# CAPT-B1-02_Cap_Touch_Matrix_FeatherWing.net
KiCad netlist of a schematic drawn in EAGLE
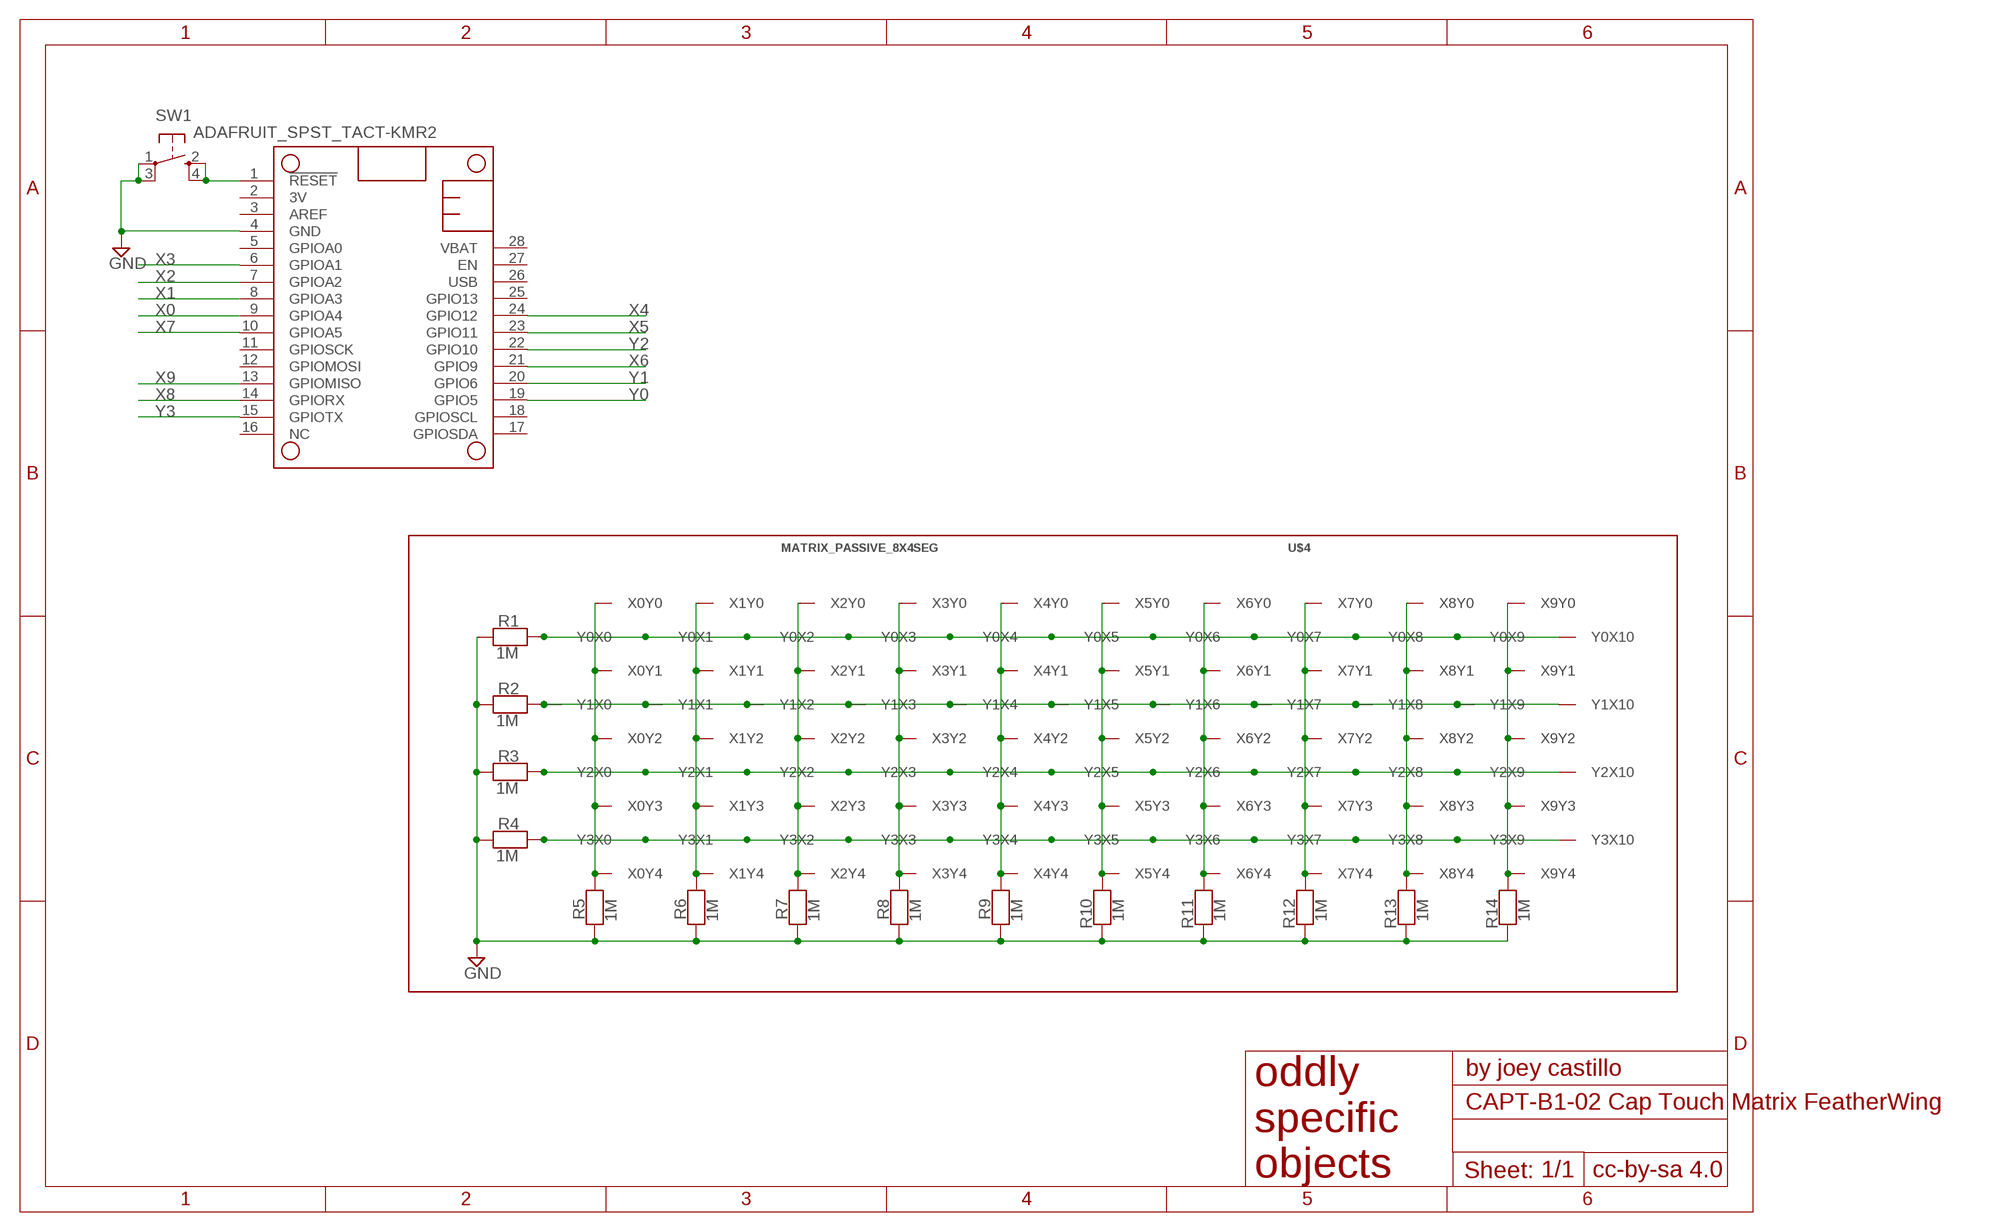
[diagram p0: schematic, sheet 1]

(export (version "E")
  (design (tool "Eeschema 10.0.6"))
  (components
    (comp (ref "MS2")
      (value "MICROBUILDER_FEATHERWING_NOHOLES")
      (footprint "eagle-import:MICROBUILDER_FEATHERWING_NOHOLES")
      (libsource (lib "eagle-import") (part "MICROBUILDER_FEATHERWING_NOHOLES"))
    )
    (comp (ref "R1")
      (value "1M")
      (footprint "eagle-import:0805_10MGAP")
      (libsource (lib "eagle-import") (part "RESISTOR0805_10MGAP"))
    )
    (comp (ref "R2")
      (value "1M")
      (footprint "eagle-import:0805_10MGAP")
      (libsource (lib "eagle-import") (part "RESISTOR0805_10MGAP"))
    )
    (comp (ref "R3")
      (value "1M")
      (footprint "eagle-import:0805_10MGAP")
      (libsource (lib "eagle-import") (part "RESISTOR0805_10MGAP"))
    )
    (comp (ref "R4")
      (value "1M")
      (footprint "eagle-import:0805_10MGAP")
      (libsource (lib "eagle-import") (part "RESISTOR0805_10MGAP"))
    )
    (comp (ref "R5")
      (value "1M")
      (footprint "eagle-import:0805_10MGAP")
      (libsource (lib "eagle-import") (part "RESISTOR0805_10MGAP"))
    )
    (comp (ref "R6")
      (value "1M")
      (footprint "eagle-import:0805_10MGAP")
      (libsource (lib "eagle-import") (part "RESISTOR0805_10MGAP"))
    )
    (comp (ref "R7")
      (value "1M")
      (footprint "eagle-import:0805_10MGAP")
      (libsource (lib "eagle-import") (part "RESISTOR0805_10MGAP"))
    )
    (comp (ref "R8")
      (value "1M")
      (footprint "eagle-import:0805_10MGAP")
      (libsource (lib "eagle-import") (part "RESISTOR0805_10MGAP"))
    )
    (comp (ref "R9")
      (value "1M")
      (footprint "eagle-import:0805_10MGAP")
      (libsource (lib "eagle-import") (part "RESISTOR0805_10MGAP"))
    )
    (comp (ref "R10")
      (value "1M")
      (footprint "eagle-import:0805_10MGAP")
      (libsource (lib "eagle-import") (part "RESISTOR0805_10MGAP"))
    )
    (comp (ref "R11")
      (value "1M")
      (footprint "eagle-import:0805_10MGAP")
      (libsource (lib "eagle-import") (part "RESISTOR0805_10MGAP"))
    )
    (comp (ref "R12")
      (value "1M")
      (footprint "eagle-import:0805_10MGAP")
      (libsource (lib "eagle-import") (part "RESISTOR0805_10MGAP"))
    )
    (comp (ref "R13")
      (value "1M")
      (footprint "eagle-import:0805_10MGAP")
      (libsource (lib "eagle-import") (part "RESISTOR0805_10MGAP"))
    )
    (comp (ref "R14")
      (value "1M")
      (footprint "eagle-import:0805_10MGAP")
      (libsource (lib "eagle-import") (part "RESISTOR0805_10MGAP"))
    )
    (comp (ref "SW1")
      (value "ADAFRUIT_SPST_TACT-KMR2")
      (footprint "eagle-import:ADAFRUIT_KMR2")
      (libsource (lib "eagle-import") (part "ADAFRUIT_SPST_TACT-KMR2"))
    )
    (comp (ref "U$4")
      (value "MATRIX_PASSIVE_8X4SEG")
      (footprint "eagle-import:MATRIX_ACTIVE_8X4SEG_4MM")
      (libsource (lib "eagle-import") (part "MATRIX_PASSIVE_8X4SEG"))
    )
  )
  (nets
    (net (code "1") (name "/3V") (class "Default")
      (node (ref "MS2") (pin "2") (pinfunction "3V_2") (pintype "power_in"))
    )
    (net (code "2") (name "/USB") (class "Default")
      (node (ref "MS2") (pin "26") (pinfunction "USB_26") (pintype "power_in"))
    )
    (net (code "3") (name "/VBAT") (class "Default")
      (node (ref "MS2") (pin "28") (pinfunction "VBAT_28") (pintype "power_in"))
    )
    (net (code "4") (name "/X0") (class "Default")
      (node (ref "MS2") (pin "9") (pinfunction "GPIOA4_9") (pintype "bidirectional"))
      (node (ref "R5") (pin "1") (pinfunction "1_1") (pintype "passive"))
      (node (ref "U$4") (pin "X0Y0") (pinfunction "X0Y0_X0Y0") (pintype "passive"))
      (node (ref "U$4") (pin "X0Y1") (pinfunction "X0Y1_X0Y1") (pintype "passive"))
      (node (ref "U$4") (pin "X0Y2") (pinfunction "X0Y2_X0Y2") (pintype "passive"))
      (node (ref "U$4") (pin "X0Y3") (pinfunction "X0Y3_X0Y3") (pintype "passive"))
      (node (ref "U$4") (pin "X0Y4") (pinfunction "X0Y4_X0Y4") (pintype "passive"))
    )
    (net (code "5") (name "/X1") (class "Default")
      (node (ref "MS2") (pin "8") (pinfunction "GPIOA3_8") (pintype "bidirectional"))
      (node (ref "R6") (pin "1") (pinfunction "1_1") (pintype "passive"))
      (node (ref "U$4") (pin "X1Y0") (pinfunction "X1Y0_X1Y0") (pintype "passive"))
      (node (ref "U$4") (pin "X1Y1") (pinfunction "X1Y1_X1Y1") (pintype "passive"))
      (node (ref "U$4") (pin "X1Y2") (pinfunction "X1Y2_X1Y2") (pintype "passive"))
      (node (ref "U$4") (pin "X1Y3") (pinfunction "X1Y3_X1Y3") (pintype "passive"))
      (node (ref "U$4") (pin "X1Y4") (pinfunction "X1Y4_X1Y4") (pintype "passive"))
    )
    (net (code "6") (name "/X2") (class "Default")
      (node (ref "MS2") (pin "7") (pinfunction "GPIOA2_7") (pintype "bidirectional"))
      (node (ref "R7") (pin "1") (pinfunction "1_1") (pintype "passive"))
      (node (ref "U$4") (pin "X2Y0") (pinfunction "X2Y0_X2Y0") (pintype "passive"))
      (node (ref "U$4") (pin "X2Y1") (pinfunction "X2Y1_X2Y1") (pintype "passive"))
      (node (ref "U$4") (pin "X2Y2") (pinfunction "X2Y2_X2Y2") (pintype "passive"))
      (node (ref "U$4") (pin "X2Y3") (pinfunction "X2Y3_X2Y3") (pintype "passive"))
      (node (ref "U$4") (pin "X2Y4") (pinfunction "X2Y4_X2Y4") (pintype "passive"))
    )
    (net (code "7") (name "/X3") (class "Default")
      (node (ref "MS2") (pin "6") (pinfunction "GPIOA1_6") (pintype "bidirectional"))
      (node (ref "R8") (pin "1") (pinfunction "1_1") (pintype "passive"))
      (node (ref "U$4") (pin "X3Y0") (pinfunction "X3Y0_X3Y0") (pintype "passive"))
      (node (ref "U$4") (pin "X3Y1") (pinfunction "X3Y1_X3Y1") (pintype "passive"))
      (node (ref "U$4") (pin "X3Y2") (pinfunction "X3Y2_X3Y2") (pintype "passive"))
      (node (ref "U$4") (pin "X3Y3") (pinfunction "X3Y3_X3Y3") (pintype "passive"))
      (node (ref "U$4") (pin "X3Y4") (pinfunction "X3Y4_X3Y4") (pintype "passive"))
    )
    (net (code "8") (name "/X4") (class "Default")
      (node (ref "MS2") (pin "24") (pinfunction "GPIO12_24") (pintype "bidirectional"))
      (node (ref "R9") (pin "1") (pinfunction "1_1") (pintype "passive"))
      (node (ref "U$4") (pin "X4Y0") (pinfunction "X4Y0_X4Y0") (pintype "passive"))
      (node (ref "U$4") (pin "X4Y1") (pinfunction "X4Y1_X4Y1") (pintype "passive"))
      (node (ref "U$4") (pin "X4Y2") (pinfunction "X4Y2_X4Y2") (pintype "passive"))
      (node (ref "U$4") (pin "X4Y3") (pinfunction "X4Y3_X4Y3") (pintype "passive"))
      (node (ref "U$4") (pin "X4Y4") (pinfunction "X4Y4_X4Y4") (pintype "passive"))
    )
    (net (code "9") (name "/X5") (class "Default")
      (node (ref "MS2") (pin "23") (pinfunction "GPIO11_23") (pintype "bidirectional"))
      (node (ref "R10") (pin "1") (pinfunction "1_1") (pintype "passive"))
      (node (ref "U$4") (pin "X5Y0") (pinfunction "X5Y0_X5Y0") (pintype "passive"))
      (node (ref "U$4") (pin "X5Y1") (pinfunction "X5Y1_X5Y1") (pintype "passive"))
      (node (ref "U$4") (pin "X5Y2") (pinfunction "X5Y2_X5Y2") (pintype "passive"))
      (node (ref "U$4") (pin "X5Y3") (pinfunction "X5Y3_X5Y3") (pintype "passive"))
      (node (ref "U$4") (pin "X5Y4") (pinfunction "X5Y4_X5Y4") (pintype "passive"))
    )
    (net (code "10") (name "/X6") (class "Default")
      (node (ref "MS2") (pin "21") (pinfunction "GPIO9_21") (pintype "bidirectional"))
      (node (ref "R11") (pin "1") (pinfunction "1_1") (pintype "passive"))
      (node (ref "U$4") (pin "X6Y0") (pinfunction "X6Y0_X6Y0") (pintype "passive"))
      (node (ref "U$4") (pin "X6Y1") (pinfunction "X6Y1_X6Y1") (pintype "passive"))
      (node (ref "U$4") (pin "X6Y2") (pinfunction "X6Y2_X6Y2") (pintype "passive"))
      (node (ref "U$4") (pin "X6Y3") (pinfunction "X6Y3_X6Y3") (pintype "passive"))
      (node (ref "U$4") (pin "X6Y4") (pinfunction "X6Y4_X6Y4") (pintype "passive"))
    )
    (net (code "11") (name "/X7") (class "Default")
      (node (ref "MS2") (pin "10") (pinfunction "GPIOA5_10") (pintype "bidirectional"))
      (node (ref "R12") (pin "1") (pinfunction "1_1") (pintype "passive"))
      (node (ref "U$4") (pin "X7Y0") (pinfunction "X7Y0_X7Y0") (pintype "passive"))
      (node (ref "U$4") (pin "X7Y1") (pinfunction "X7Y1_X7Y1") (pintype "passive"))
      (node (ref "U$4") (pin "X7Y2") (pinfunction "X7Y2_X7Y2") (pintype "passive"))
      (node (ref "U$4") (pin "X7Y3") (pinfunction "X7Y3_X7Y3") (pintype "passive"))
      (node (ref "U$4") (pin "X7Y4") (pinfunction "X7Y4_X7Y4") (pintype "passive"))
    )
    (net (code "12") (name "/X8") (class "Default")
      (node (ref "MS2") (pin "14") (pinfunction "GPIORX_14") (pintype "bidirectional"))
      (node (ref "R13") (pin "1") (pinfunction "1_1") (pintype "passive"))
      (node (ref "U$4") (pin "X8Y0") (pinfunction "X8Y0_X8Y0") (pintype "passive"))
      (node (ref "U$4") (pin "X8Y1") (pinfunction "X8Y1_X8Y1") (pintype "passive"))
      (node (ref "U$4") (pin "X8Y2") (pinfunction "X8Y2_X8Y2") (pintype "passive"))
      (node (ref "U$4") (pin "X8Y3") (pinfunction "X8Y3_X8Y3") (pintype "passive"))
      (node (ref "U$4") (pin "X8Y4") (pinfunction "X8Y4_X8Y4") (pintype "passive"))
    )
    (net (code "13") (name "/X9") (class "Default")
      (node (ref "MS2") (pin "13") (pinfunction "GPIOMISO_13") (pintype "bidirectional"))
      (node (ref "R14") (pin "1") (pinfunction "1_1") (pintype "passive"))
      (node (ref "U$4") (pin "X9Y0") (pinfunction "X9Y0_X9Y0") (pintype "passive"))
      (node (ref "U$4") (pin "X9Y1") (pinfunction "X9Y1_X9Y1") (pintype "passive"))
      (node (ref "U$4") (pin "X9Y2") (pinfunction "X9Y2_X9Y2") (pintype "passive"))
      (node (ref "U$4") (pin "X9Y3") (pinfunction "X9Y3_X9Y3") (pintype "passive"))
      (node (ref "U$4") (pin "X9Y4") (pinfunction "X9Y4_X9Y4") (pintype "passive"))
    )
    (net (code "14") (name "/Y0") (class "Default")
      (node (ref "MS2") (pin "19") (pinfunction "GPIO5_19") (pintype "bidirectional"))
      (node (ref "R1") (pin "1") (pinfunction "1_1") (pintype "passive"))
      (node (ref "U$4") (pin "Y0X0") (pinfunction "Y0X0_Y0X0") (pintype "passive"))
      (node (ref "U$4") (pin "Y0X1") (pinfunction "Y0X1_Y0X1") (pintype "passive"))
      (node (ref "U$4") (pin "Y0X10") (pinfunction "Y0X10_Y0X10") (pintype "passive"))
      (node (ref "U$4") (pin "Y0X2") (pinfunction "Y0X2_Y0X2") (pintype "passive"))
      (node (ref "U$4") (pin "Y0X3") (pinfunction "Y0X3_Y0X3") (pintype "passive"))
      (node (ref "U$4") (pin "Y0X4") (pinfunction "Y0X4_Y0X4") (pintype "passive"))
      (node (ref "U$4") (pin "Y0X5") (pinfunction "Y0X5_Y0X5") (pintype "passive"))
      (node (ref "U$4") (pin "Y0X6") (pinfunction "Y0X6_Y0X6") (pintype "passive"))
      (node (ref "U$4") (pin "Y0X7") (pinfunction "Y0X7_Y0X7") (pintype "passive"))
      (node (ref "U$4") (pin "Y0X8") (pinfunction "Y0X8_Y0X8") (pintype "passive"))
      (node (ref "U$4") (pin "Y0X9") (pinfunction "Y0X9_Y0X9") (pintype "passive"))
    )
    (net (code "15") (name "/Y1") (class "Default")
      (node (ref "MS2") (pin "20") (pinfunction "GPIO6_20") (pintype "bidirectional"))
      (node (ref "R2") (pin "1") (pinfunction "1_1") (pintype "passive"))
      (node (ref "U$4") (pin "Y1X0") (pinfunction "Y1X0_Y1X0") (pintype "passive"))
      (node (ref "U$4") (pin "Y1X1") (pinfunction "Y1X1_Y1X1") (pintype "passive"))
      (node (ref "U$4") (pin "Y1X10") (pinfunction "Y1X10_Y1X10") (pintype "passive"))
      (node (ref "U$4") (pin "Y1X2") (pinfunction "Y1X2_Y1X2") (pintype "passive"))
      (node (ref "U$4") (pin "Y1X3") (pinfunction "Y1X3_Y1X3") (pintype "passive"))
      (node (ref "U$4") (pin "Y1X4") (pinfunction "Y1X4_Y1X4") (pintype "passive"))
      (node (ref "U$4") (pin "Y1X5") (pinfunction "Y1X5_Y1X5") (pintype "passive"))
      (node (ref "U$4") (pin "Y1X6") (pinfunction "Y1X6_Y1X6") (pintype "passive"))
      (node (ref "U$4") (pin "Y1X7") (pinfunction "Y1X7_Y1X7") (pintype "passive"))
      (node (ref "U$4") (pin "Y1X8") (pinfunction "Y1X8_Y1X8") (pintype "passive"))
      (node (ref "U$4") (pin "Y1X9") (pinfunction "Y1X9_Y1X9") (pintype "passive"))
    )
    (net (code "16") (name "/Y2") (class "Default")
      (node (ref "MS2") (pin "22") (pinfunction "GPIO10_22") (pintype "bidirectional"))
      (node (ref "R3") (pin "1") (pinfunction "1_1") (pintype "passive"))
      (node (ref "U$4") (pin "Y2X0") (pinfunction "Y2X0_Y2X0") (pintype "passive"))
      (node (ref "U$4") (pin "Y2X1") (pinfunction "Y2X1_Y2X1") (pintype "passive"))
      (node (ref "U$4") (pin "Y2X10") (pinfunction "Y2X10_Y2X10") (pintype "passive"))
      (node (ref "U$4") (pin "Y2X2") (pinfunction "Y2X2_Y2X2") (pintype "passive"))
      (node (ref "U$4") (pin "Y2X3") (pinfunction "Y2X3_Y2X3") (pintype "passive"))
      (node (ref "U$4") (pin "Y2X4") (pinfunction "Y2X4_Y2X4") (pintype "passive"))
      (node (ref "U$4") (pin "Y2X5") (pinfunction "Y2X5_Y2X5") (pintype "passive"))
      (node (ref "U$4") (pin "Y2X6") (pinfunction "Y2X6_Y2X6") (pintype "passive"))
      (node (ref "U$4") (pin "Y2X7") (pinfunction "Y2X7_Y2X7") (pintype "passive"))
      (node (ref "U$4") (pin "Y2X8") (pinfunction "Y2X8_Y2X8") (pintype "passive"))
      (node (ref "U$4") (pin "Y2X9") (pinfunction "Y2X9_Y2X9") (pintype "passive"))
    )
    (net (code "17") (name "/Y3") (class "Default")
      (node (ref "MS2") (pin "15") (pinfunction "GPIOTX_15") (pintype "bidirectional"))
      (node (ref "R4") (pin "1") (pinfunction "1_1") (pintype "passive"))
      (node (ref "U$4") (pin "Y3X0") (pinfunction "Y3X0_Y3X0") (pintype "passive"))
      (node (ref "U$4") (pin "Y3X1") (pinfunction "Y3X1_Y3X1") (pintype "passive"))
      (node (ref "U$4") (pin "Y3X10") (pinfunction "Y3X10_Y3X10") (pintype "passive"))
      (node (ref "U$4") (pin "Y3X2") (pinfunction "Y3X2_Y3X2") (pintype "passive"))
      (node (ref "U$4") (pin "Y3X3") (pinfunction "Y3X3_Y3X3") (pintype "passive"))
      (node (ref "U$4") (pin "Y3X4") (pinfunction "Y3X4_Y3X4") (pintype "passive"))
      (node (ref "U$4") (pin "Y3X5") (pinfunction "Y3X5_Y3X5") (pintype "passive"))
      (node (ref "U$4") (pin "Y3X6") (pinfunction "Y3X6_Y3X6") (pintype "passive"))
      (node (ref "U$4") (pin "Y3X7") (pinfunction "Y3X7_Y3X7") (pintype "passive"))
      (node (ref "U$4") (pin "Y3X8") (pinfunction "Y3X8_Y3X8") (pintype "passive"))
      (node (ref "U$4") (pin "Y3X9") (pinfunction "Y3X9_Y3X9") (pintype "passive"))
    )
    (net (code "18") (name "GND") (class "Default")
      (node (ref "MS2") (pin "4") (pinfunction "GND_4") (pintype "power_in"))
      (node (ref "R1") (pin "2") (pinfunction "2_2") (pintype "passive"))
      (node (ref "R10") (pin "2") (pinfunction "2_2") (pintype "passive"))
      (node (ref "R11") (pin "2") (pinfunction "2_2") (pintype "passive"))
      (node (ref "R12") (pin "2") (pinfunction "2_2") (pintype "passive"))
      (node (ref "R13") (pin "2") (pinfunction "2_2") (pintype "passive"))
      (node (ref "R14") (pin "2") (pinfunction "2_2") (pintype "passive"))
      (node (ref "R2") (pin "2") (pinfunction "2_2") (pintype "passive"))
      (node (ref "R3") (pin "2") (pinfunction "2_2") (pintype "passive"))
      (node (ref "R4") (pin "2") (pinfunction "2_2") (pintype "passive"))
      (node (ref "R5") (pin "2") (pinfunction "2_2") (pintype "passive"))
      (node (ref "R6") (pin "2") (pinfunction "2_2") (pintype "passive"))
      (node (ref "R7") (pin "2") (pinfunction "2_2") (pintype "passive"))
      (node (ref "R8") (pin "2") (pinfunction "2_2") (pintype "passive"))
      (node (ref "R9") (pin "2") (pinfunction "2_2") (pintype "passive"))
      (node (ref "SW1") (pin "1") (pinfunction "P_1") (pintype "passive"))
      (node (ref "SW1") (pin "3") (pinfunction "P1_3") (pintype "passive"))
    )
    (net (code "19") (name "Net-(MS2-~{RESET})") (class "Default")
      (node (ref "MS2") (pin "1") (pinfunction "~{RESET}_1") (pintype "input"))
      (node (ref "SW1") (pin "2") (pinfunction "S_2") (pintype "passive"))
      (node (ref "SW1") (pin "4") (pinfunction "S1_4") (pintype "passive"))
    )
    (net (code "20") (name "unconnected-(MS2-AREF-Pad3)") (class "Default")
      (node (ref "MS2") (pin "3") (pinfunction "AREF_3") (pintype "passive"))
    )
    (net (code "21") (name "unconnected-(MS2-EN-Pad27)") (class "Default")
      (node (ref "MS2") (pin "27") (pinfunction "EN_27") (pintype "passive"))
    )
    (net (code "22") (name "unconnected-(MS2-GPIO13-Pad25)") (class "Default")
      (node (ref "MS2") (pin "25") (pinfunction "GPIO13_25") (pintype "bidirectional"))
    )
    (net (code "23") (name "unconnected-(MS2-GPIOA0-Pad5)") (class "Default")
      (node (ref "MS2") (pin "5") (pinfunction "GPIOA0_5") (pintype "bidirectional"))
    )
    (net (code "24") (name "unconnected-(MS2-GPIOMOSI-Pad12)") (class "Default")
      (node (ref "MS2") (pin "12") (pinfunction "GPIOMOSI_12") (pintype "bidirectional"))
    )
    (net (code "25") (name "unconnected-(MS2-GPIOSCK-Pad11)") (class "Default")
      (node (ref "MS2") (pin "11") (pinfunction "GPIOSCK_11") (pintype "bidirectional"))
    )
    (net (code "26") (name "unconnected-(MS2-GPIOSCL-Pad18)") (class "Default")
      (node (ref "MS2") (pin "18") (pinfunction "GPIOSCL_18") (pintype "bidirectional"))
    )
    (net (code "27") (name "unconnected-(MS2-GPIOSDA-Pad17)") (class "Default")
      (node (ref "MS2") (pin "17") (pinfunction "GPIOSDA_17") (pintype "bidirectional"))
    )
    (net (code "28") (name "unconnected-(MS2-NC-Pad16)") (class "Default")
      (node (ref "MS2") (pin "16") (pinfunction "NC_16") (pintype "passive"))
    )
  )
)
